# Adafruit_Trinket_3V_microUSB.net
KiCad netlist of a schematic drawn in EAGLE
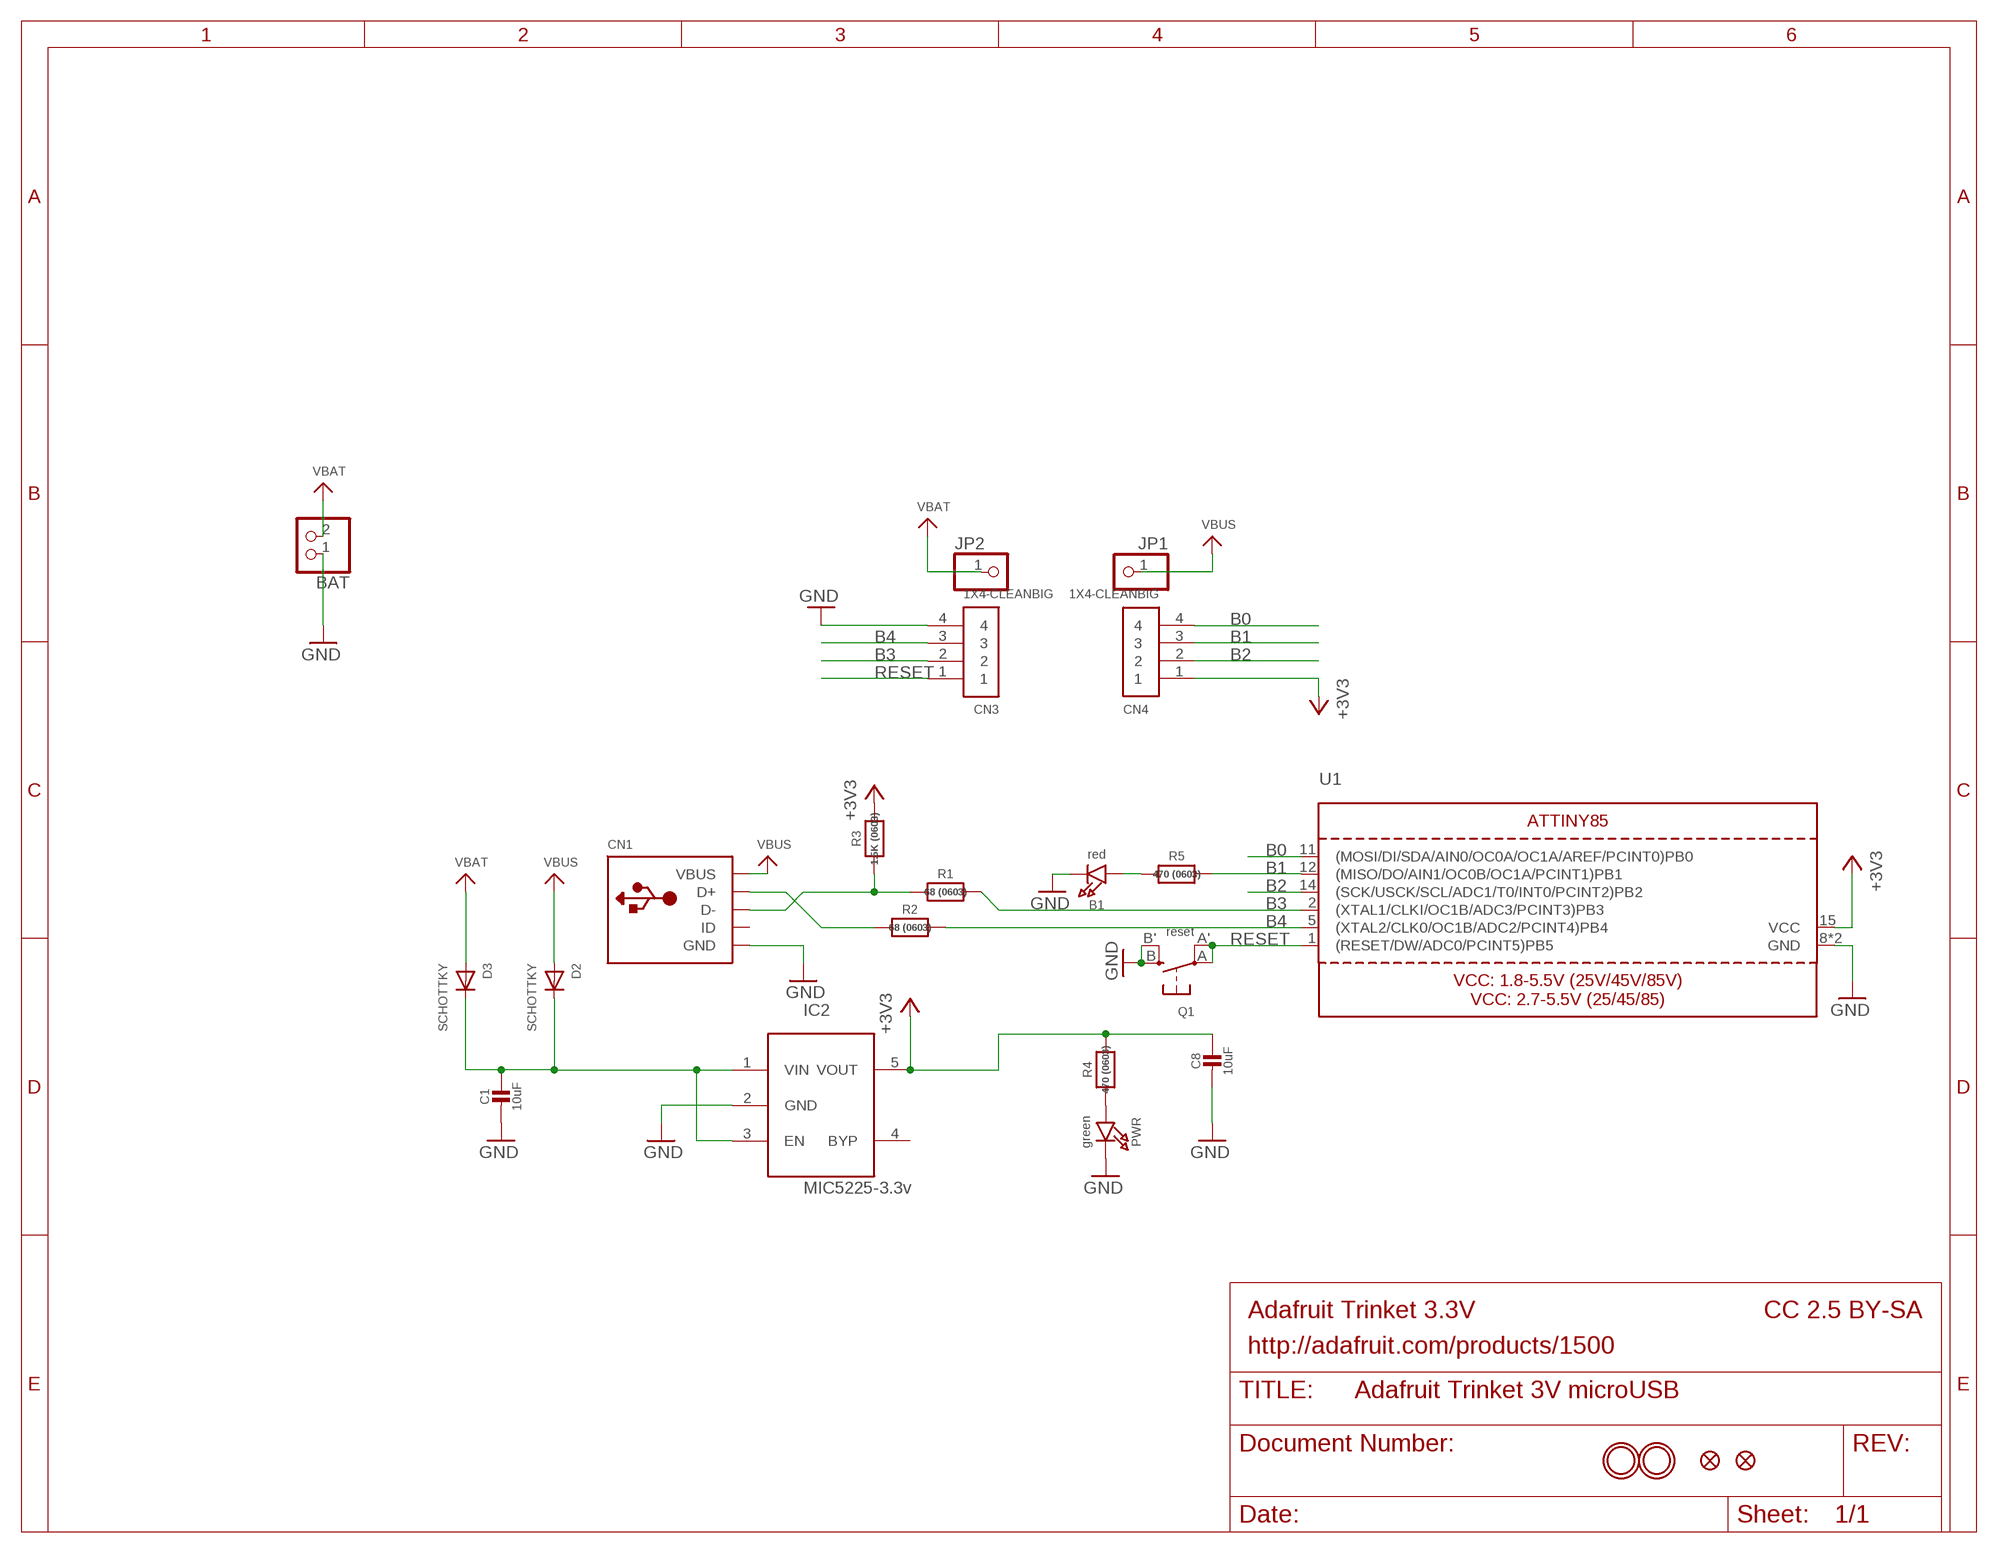
[diagram p0: schematic, sheet 1]

(export (version "E")
  (design (tool "Eeschema 10.0.6"))
  (components
    (comp (ref "B1")
      (value "red")
      (footprint "eagle-import:CHIPLED_0805_NOOUTLINE")
      (libsource (lib "eagle-import") (part "LED0805_NOOUTLINE"))
    )
    (comp (ref "BAT")
      (value "CON_JST_PH_2PIN")
      (footprint "eagle-import:JSTPH2")
      (libsource (lib "eagle-import") (part "CON_JST_PH_2PIN"))
    )
    (comp (ref "C1")
      (value "10uF")
      (footprint "eagle-import:0805-NO")
      (libsource (lib "eagle-import") (part "CAP_CERAMIC0805-NOOUTLINE"))
    )
    (comp (ref "C8")
      (value "10uF")
      (footprint "eagle-import:0805-NO")
      (libsource (lib "eagle-import") (part "CAP_CERAMIC0805-NOOUTLINE"))
    )
    (comp (ref "CN1")
      (value "USBMICRO_20329")
      (footprint "eagle-import:4UCONN_20329")
      (libsource (lib "eagle-import") (part "USBMICRO_20329"))
    )
    (comp (ref "CN3")
      (value "1X4-CLEANBIG")
      (footprint "eagle-import:1X04-CLEANBIG")
      (libsource (lib "eagle-import") (part "1X4-CLEANBIG"))
    )
    (comp (ref "CN4")
      (value "1X4-CLEANBIG")
      (footprint "eagle-import:1X04-CLEANBIG")
      (libsource (lib "eagle-import") (part "1X4-CLEANBIG"))
    )
    (comp (ref "D2")
      (value "SCHOTTKY")
      (footprint "eagle-import:SOD-123FL")
      (libsource (lib "eagle-import") (part "DIODE_SOD-123FL"))
    )
    (comp (ref "D3")
      (value "SCHOTTKY")
      (footprint "eagle-import:SOD-123FL")
      (libsource (lib "eagle-import") (part "DIODE_SOD-123FL"))
    )
    (comp (ref "IC2")
      (value "MIC5225-3.3v")
      (footprint "eagle-import:SOT23-5L")
      (libsource (lib "eagle-import") (part "LP298XS"))
    )
    (comp (ref "JP1")
      (value "PINHD-1X1CB")
      (footprint "eagle-import:1X01-CLEANBIG")
      (libsource (lib "eagle-import") (part "PINHD-1X1CB"))
    )
    (comp (ref "JP2")
      (value "PINHD-1X1CB")
      (footprint "eagle-import:1X01-CLEANBIG")
      (libsource (lib "eagle-import") (part "PINHD-1X1CB"))
    )
    (comp (ref "PWR")
      (value "green")
      (footprint "eagle-import:CHIPLED_0805_NOOUTLINE")
      (libsource (lib "eagle-import") (part "LED0805_NOOUTLINE"))
    )
    (comp (ref "Q1")
      (value "reset")
      (footprint "eagle-import:BTN_KMR2_4.6X2.8")
      (libsource (lib "eagle-import") (part "SWITCH_TACT_SMT4.6X2.8"))
    )
    (comp (ref "R1")
      (value "68 (0603)")
      (footprint "eagle-import:0603-NO")
      (libsource (lib "eagle-import") (part "RESISTOR_0603_NOOUT"))
    )
    (comp (ref "R2")
      (value "68 (0603)")
      (footprint "eagle-import:0603-NO")
      (libsource (lib "eagle-import") (part "RESISTOR_0603_NOOUT"))
    )
    (comp (ref "R3")
      (value "1.5K (0603)")
      (footprint "eagle-import:0603-NO")
      (libsource (lib "eagle-import") (part "RESISTOR_0603_NOOUT"))
    )
    (comp (ref "R4")
      (value "470 (0603)")
      (footprint "eagle-import:0603-NO")
      (libsource (lib "eagle-import") (part "RESISTOR_0603_NOOUT"))
    )
    (comp (ref "R5")
      (value "470 (0603)")
      (footprint "eagle-import:0603-NO")
      (libsource (lib "eagle-import") (part "RESISTOR_0603_NOOUT"))
    )
    (comp (ref "U$1")
      (value "FIDUCIAL\"\"")
      (footprint "eagle-import:FIDUCIAL_1MM")
      (libsource (lib "eagle-import") (part "FIDUCIAL{dblquote}{dblquote}"))
    )
    (comp (ref "U$6")
      (value "FIDUCIAL\"\"")
      (footprint "eagle-import:FIDUCIAL_1MM")
      (libsource (lib "eagle-import") (part "FIDUCIAL{dblquote}{dblquote}"))
    )
    (comp (ref "U$8")
      (value "MOUNTINGHOLE2.0")
      (footprint "eagle-import:MOUNTINGHOLE_2.0_PLATED")
      (libsource (lib "eagle-import") (part "MOUNTINGHOLE2.0"))
    )
    (comp (ref "U$9")
      (value "MOUNTINGHOLE2.0")
      (footprint "eagle-import:MOUNTINGHOLE_2.0_PLATED")
      (libsource (lib "eagle-import") (part "MOUNTINGHOLE2.0"))
    )
    (comp (ref "U1")
      (value "ATTINY85")
      (footprint "eagle-import:MLF20_4X4MM_0.5MM_ATMEL")
      (libsource (lib "eagle-import") (part "ATTINY85"))
    )
  )
  (nets
    (net (code "1") (name "+3V3") (class "Default")
      (node (ref "C8") (pin "1") (pinfunction "1_1") (pintype "passive"))
      (node (ref "CN4") (pin "1") (pinfunction "1_1") (pintype "bidirectional"))
      (node (ref "IC2") (pin "5") (pinfunction "VOUT_5") (pintype "bidirectional"))
      (node (ref "R3") (pin "2") (pinfunction "2_2") (pintype "passive"))
      (node (ref "R4") (pin "2") (pinfunction "2_2") (pintype "passive"))
      (node (ref "U1") (pin "15") (pinfunction "VCC_15") (pintype "power_in"))
    )
    (net (code "2") (name "/B0") (class "Default")
      (node (ref "CN4") (pin "4") (pinfunction "4_4") (pintype "bidirectional"))
      (node (ref "U1") (pin "11") (pinfunction "(MOSI/DI/SDA/AIN0/OC0A/OC1A/AREF/PCINT0)PB0_11") (pintype "bidirectional"))
    )
    (net (code "3") (name "/B1") (class "Default")
      (node (ref "CN4") (pin "3") (pinfunction "3_3") (pintype "bidirectional"))
      (node (ref "R5") (pin "2") (pinfunction "2_2") (pintype "passive"))
      (node (ref "U1") (pin "12") (pinfunction "(MISO/DO/AIN1/OC0B/OC1A/PCINT1)PB1_12") (pintype "bidirectional"))
    )
    (net (code "4") (name "/B2") (class "Default")
      (node (ref "CN4") (pin "2") (pinfunction "2_2") (pintype "bidirectional"))
      (node (ref "U1") (pin "14") (pinfunction "(SCK/USCK/SCL/ADC1/T0/INT0/PCINT2)PB2_14") (pintype "bidirectional"))
    )
    (net (code "5") (name "/B3") (class "Default")
      (node (ref "CN3") (pin "2") (pinfunction "2_2") (pintype "bidirectional"))
      (node (ref "R1") (pin "2") (pinfunction "2_2") (pintype "passive"))
      (node (ref "U1") (pin "2") (pinfunction "(XTAL1/CLKI/OC1B/ADC3/PCINT3)PB3_2") (pintype "bidirectional"))
    )
    (net (code "6") (name "/B4") (class "Default")
      (node (ref "CN3") (pin "3") (pinfunction "3_3") (pintype "bidirectional"))
      (node (ref "R2") (pin "2") (pinfunction "2_2") (pintype "passive"))
      (node (ref "U1") (pin "5") (pinfunction "(XTAL2/CLK0/OC1B/ADC2/PCINT4)PB4_5") (pintype "bidirectional"))
    )
    (net (code "7") (name "/RESET") (class "Default")
      (node (ref "CN3") (pin "1") (pinfunction "1_1") (pintype "bidirectional"))
      (node (ref "Q1") (pin "A") (pinfunction "P_A") (pintype "passive"))
      (node (ref "Q1") (pin "A'") (pinfunction "P1_A'") (pintype "passive"))
      (node (ref "U1") (pin "1") (pinfunction "(RESET/DW/ADC0/PCINT5)PB5_1") (pintype "bidirectional"))
    )
    (net (code "8") (name "GND") (class "Default")
      (node (ref "B1") (pin "C") (pinfunction "C_C") (pintype "passive"))
      (node (ref "BAT") (pin "1") (pinfunction "1_1") (pintype "passive"))
      (node (ref "C1") (pin "2") (pinfunction "2_2") (pintype "passive"))
      (node (ref "C8") (pin "2") (pinfunction "2_2") (pintype "passive"))
      (node (ref "CN1") (pin "BASE@1") (pinfunction "GND_BASE@1") (pintype "power_in"))
      (node (ref "CN1") (pin "BASE@2") (pinfunction "GND_BASE@2") (pintype "power_in"))
      (node (ref "CN1") (pin "GND") (pinfunction "GND_GND") (pintype "power_in"))
      (node (ref "CN1") (pin "SPRT@1") (pinfunction "GND_SPRT@1") (pintype "power_in"))
      (node (ref "CN1") (pin "SPRT@2") (pinfunction "GND_SPRT@2") (pintype "power_in"))
      (node (ref "CN1") (pin "SPRT@3") (pinfunction "GND_SPRT@3") (pintype "power_in"))
      (node (ref "CN1") (pin "SPRT@4") (pinfunction "GND_SPRT@4") (pintype "power_in"))
      (node (ref "CN3") (pin "4") (pinfunction "4_4") (pintype "bidirectional"))
      (node (ref "IC2") (pin "2") (pinfunction "GND_2") (pintype "bidirectional"))
      (node (ref "PWR") (pin "C") (pinfunction "C_C") (pintype "passive"))
      (node (ref "Q1") (pin "B") (pinfunction "S_B") (pintype "passive"))
      (node (ref "Q1") (pin "B'") (pinfunction "S1_B'") (pintype "passive"))
      (node (ref "U1") (pin "8") (pinfunction "GND_8") (pintype "power_in"))
      (node (ref "U1") (pin "THERMAL") (pinfunction "GND_THERMAL") (pintype "power_in"))
    )
    (net (code "9") (name "Net-(B1-PadA)") (class "Default")
      (node (ref "B1") (pin "A") (pinfunction "A_A") (pintype "passive"))
      (node (ref "R5") (pin "1") (pinfunction "1_1") (pintype "passive"))
    )
    (net (code "10") (name "Net-(CN1-PadD+)") (class "Default")
      (node (ref "CN1") (pin "D+") (pinfunction "D+_D+") (pintype "bidirectional"))
      (node (ref "R2") (pin "1") (pinfunction "1_1") (pintype "passive"))
    )
    (net (code "11") (name "Net-(CN1-PadD-)") (class "Default")
      (node (ref "CN1") (pin "D-") (pinfunction "D-_D-") (pintype "bidirectional"))
      (node (ref "R1") (pin "1") (pinfunction "1_1") (pintype "passive"))
      (node (ref "R3") (pin "1") (pinfunction "1_1") (pintype "passive"))
    )
    (net (code "12") (name "Net-(IC2-EN)") (class "Default")
      (node (ref "C1") (pin "1") (pinfunction "1_1") (pintype "passive"))
      (node (ref "D2") (pin "C") (pinfunction "C_C") (pintype "passive"))
      (node (ref "D3") (pin "C") (pinfunction "C_C") (pintype "passive"))
      (node (ref "IC2") (pin "1") (pinfunction "VIN_1") (pintype "bidirectional"))
      (node (ref "IC2") (pin "3") (pinfunction "EN_3") (pintype "bidirectional"))
    )
    (net (code "13") (name "Net-(PWR-PadA)") (class "Default")
      (node (ref "PWR") (pin "A") (pinfunction "A_A") (pintype "passive"))
      (node (ref "R4") (pin "1") (pinfunction "1_1") (pintype "passive"))
    )
    (net (code "14") (name "VBAT") (class "Default")
      (node (ref "BAT") (pin "2") (pinfunction "2_2") (pintype "passive"))
      (node (ref "D3") (pin "A") (pinfunction "A_A") (pintype "passive"))
      (node (ref "JP2") (pin "1") (pinfunction "1_1") (pintype "passive"))
    )
    (net (code "15") (name "VBUS") (class "Default")
      (node (ref "CN1") (pin "VBUS") (pinfunction "VBUS_VBUS") (pintype "power_in"))
      (node (ref "D2") (pin "A") (pinfunction "A_A") (pintype "passive"))
      (node (ref "JP1") (pin "1") (pinfunction "1_1") (pintype "passive"))
    )
    (net (code "16") (name "unconnected-(CN1-PadID)") (class "Default")
      (node (ref "CN1") (pin "ID") (pinfunction "ID_ID") (pintype "bidirectional"))
    )
    (net (code "17") (name "unconnected-(IC2-BYP-Pad4)") (class "Default")
      (node (ref "IC2") (pin "4") (pinfunction "BYP_4") (pintype "bidirectional"))
    )
  )
)
